# 09_AD.net
KiCad netlist of a schematic drawn in Altium Designer
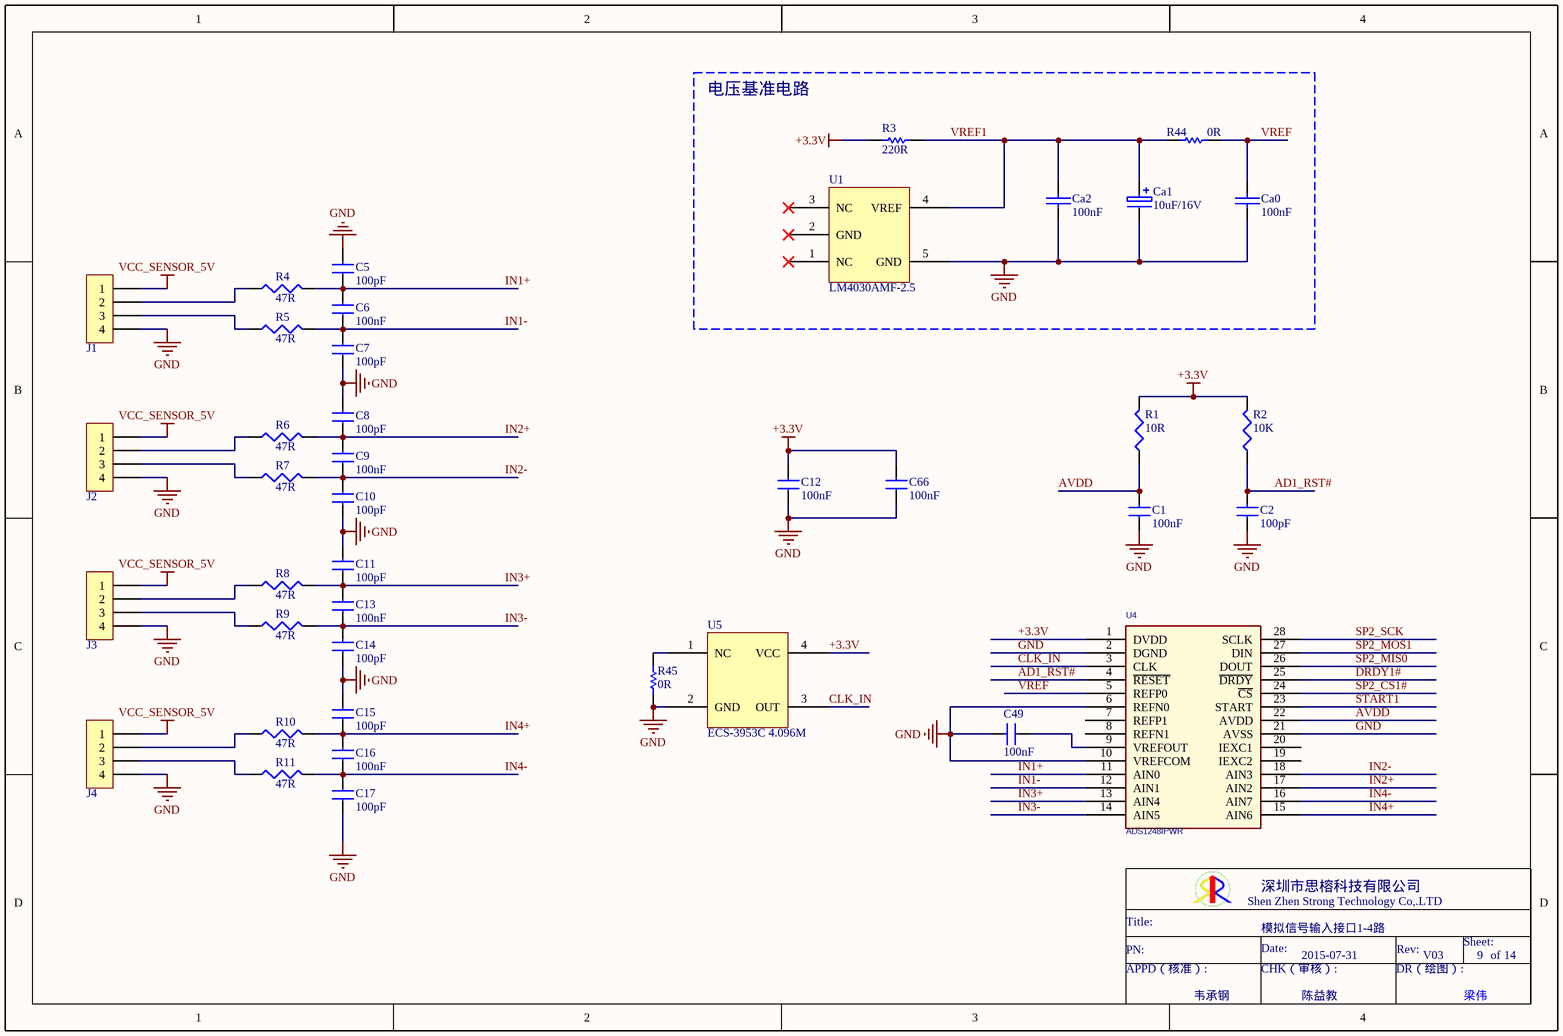
[diagram p0: 09_AD.SchDoc]

(export (version "E")
  (design (tool "Eeschema 10.0.6"))
  (components
    (comp (ref "C1")
      (value "100nF")
      (footprint "0603C")
      (description "Capacitor")
      (libsource (lib "*") (part "电容"))
    )
    (comp (ref "C2")
      (value "100pF")
      (footprint "0603C")
      (description "Capacitor")
      (libsource (lib "*") (part "电容"))
    )
    (comp (ref "C5")
      (value "100pF")
      (footprint "0603C")
      (description "Capacitor")
      (libsource (lib "*") (part "电容"))
    )
    (comp (ref "C6")
      (value "100nF")
      (footprint "0603C")
      (description "Capacitor")
      (libsource (lib "*") (part "电容"))
    )
    (comp (ref "C7")
      (value "100pF")
      (footprint "0603C")
      (description "Capacitor")
      (libsource (lib "*") (part "电容"))
    )
    (comp (ref "C8")
      (value "100pF")
      (footprint "0603C")
      (description "Capacitor")
      (libsource (lib "*") (part "电容"))
    )
    (comp (ref "C9")
      (value "100nF")
      (footprint "0603C")
      (description "Capacitor")
      (libsource (lib "*") (part "电容"))
    )
    (comp (ref "C10")
      (value "100pF")
      (footprint "0603C")
      (description "Capacitor")
      (libsource (lib "*") (part "电容"))
    )
    (comp (ref "C11")
      (value "100pF")
      (footprint "0603C")
      (description "Capacitor")
      (libsource (lib "*") (part "电容"))
    )
    (comp (ref "C12")
      (value "100nF")
      (footprint "0603C")
      (description "Capacitor")
      (libsource (lib "*") (part "电容"))
    )
    (comp (ref "C13")
      (value "100nF")
      (footprint "0603C")
      (description "Capacitor")
      (libsource (lib "*") (part "电容"))
    )
    (comp (ref "C14")
      (value "100pF")
      (footprint "0603C")
      (description "Capacitor")
      (libsource (lib "*") (part "电容"))
    )
    (comp (ref "C15")
      (value "100pF")
      (footprint "0603C")
      (description "Capacitor")
      (libsource (lib "*") (part "电容"))
    )
    (comp (ref "C16")
      (value "100nF")
      (footprint "0603C")
      (description "Capacitor")
      (libsource (lib "*") (part "电容"))
    )
    (comp (ref "C17")
      (value "100pF")
      (footprint "0603C")
      (description "Capacitor")
      (libsource (lib "*") (part "电容"))
    )
    (comp (ref "C49")
      (value "100nF")
      (footprint "0603C")
      (description "Capacitor")
      (libsource (lib "*") (part "电容"))
    )
    (comp (ref "C66")
      (value "100nF")
      (footprint "0603C")
      (description "Capacitor")
      (libsource (lib "*") (part "电容"))
    )
    (comp (ref "Ca0") (value "100nF") (footprint "0603C") (libsource (lib "WeiCHGSCH") (part "CAP")))
    (comp (ref "Ca1") (value "10uF/16V") (footprint "A") (libsource (lib "WeiCHGSCH") (part "CAP2")))
    (comp (ref "Ca2") (value "100nF") (footprint "0603C") (libsource (lib "WeiCHGSCH") (part "CAP")))
    (comp (ref "J1") (value "XH-4A") (footprint "CN4-2.54") (libsource (lib "Mylibrary") (part "CON4")))
    (comp (ref "J2") (value "XH-4A") (footprint "CN4-2.54") (libsource (lib "Mylibrary") (part "CON4")))
    (comp (ref "J3") (value "XH-4A") (footprint "CN4-2.54") (libsource (lib "Mylibrary") (part "CON4")))
    (comp (ref "J4") (value "XH-4A") (footprint "CN4-2.54") (libsource (lib "Mylibrary") (part "CON4")))
    (comp (ref "R1") (value "10R") (footprint "0603R") (libsource (lib "*") (part "RES1")))
    (comp (ref "R2") (value "10K") (footprint "0603R") (libsource (lib "*") (part "RES1")))
    (comp (ref "R3") (value "220R") (footprint "0603R") (libsource (lib "Mylibrary") (part "RES")))
    (comp (ref "R4") (value "47R") (footprint "0603R") (libsource (lib "*") (part "RES1")))
    (comp (ref "R5") (value "47R") (footprint "0603R") (libsource (lib "*") (part "RES1")))
    (comp (ref "R6") (value "47R") (footprint "0603R") (libsource (lib "*") (part "RES1")))
    (comp (ref "R7") (value "47R") (footprint "0603R") (libsource (lib "*") (part "RES1")))
    (comp (ref "R8") (value "47R") (footprint "0603R") (libsource (lib "*") (part "RES1")))
    (comp (ref "R9") (value "47R") (footprint "0603R") (libsource (lib "*") (part "RES1")))
    (comp (ref "R10") (value "47R") (footprint "0603R") (libsource (lib "*") (part "RES1")))
    (comp (ref "R11") (value "47R") (footprint "0603R") (libsource (lib "*") (part "RES1")))
    (comp (ref "R44") (value "0R") (footprint "0603R") (libsource (lib "Mylibrary") (part "RES")))
    (comp (ref "R45") (value "0R") (footprint "0603R") (libsource (lib "Mylibrary") (part "RES")))
    (comp (ref "U1")
      (value "LM4030AMF-2.5")
      (footprint "SOT23-5")
      (description "Voltage adj")
      (fields (field (name "PUBLISHER") "Altium Limited"))
      (libsource (lib "Mylibrary") (part "LM4030"))
    )
    (comp (ref "U4")
      (value "ADS1248IPWR")
      (footprint "SOIC28")
      (description "IC - 10 BIT FET BUS SWITCH")
      (fields (field (name "MANUFACTURER") "Texas Instruments"))
      (libsource (lib "Mylibrary") (part "ADS1248IPWR"))
    )
    (comp (ref "U5")
      (value "ECS-3953C 4.096M")
      (footprint "ECS-3953C")
      (description "贴片晶振")
      (fields (field (name "PUBLISHER") "Altium Limited"))
      (libsource (lib "Mylibrary") (part "ECS-3953C"))
    )
  )
  (nets
    (net (code "1") (name "+3.3V") (class "Default")
      (node (ref "C12") (pin "1") (pinfunction "1_1") (pintype "passive"))
      (node (ref "C66") (pin "2") (pinfunction "2_2") (pintype "passive"))
      (node (ref "R1") (pin "2") (pinfunction "2_2") (pintype "passive"))
      (node (ref "R2") (pin "2") (pinfunction "2_2") (pintype "passive"))
      (node (ref "R3") (pin "2") (pinfunction "2_2") (pintype "passive"))
      (node (ref "U4") (pin "1") (pinfunction "DVDD_1") (pintype "passive"))
      (node (ref "U5") (pin "4") (pinfunction "VCC_4") (pintype "passive"))
    )
    (net (code "2") (name "/AD1_RST#") (class "Default")
      (node (ref "C2") (pin "1") (pinfunction "1_1") (pintype "passive"))
      (node (ref "R2") (pin "1") (pinfunction "1_1") (pintype "passive"))
      (node (ref "U4") (pin "4") (pinfunction "~{RESET}_4") (pintype "passive"))
    )
    (net (code "3") (name "/AVDD") (class "Default")
      (node (ref "C1") (pin "1") (pinfunction "1_1") (pintype "passive"))
      (node (ref "R1") (pin "1") (pinfunction "1_1") (pintype "passive"))
      (node (ref "U4") (pin "22") (pinfunction "AVDD_22") (pintype "passive"))
    )
    (net (code "4") (name "/CLK_IN") (class "Default")
      (node (ref "U4") (pin "3") (pinfunction "CLK_3") (pintype "passive"))
      (node (ref "U5") (pin "3") (pinfunction "OUT_3") (pintype "passive"))
    )
    (net (code "5") (name "/DRDY1#") (class "Default")
      (node (ref "U4") (pin "25") (pinfunction "~{DRDY}_25") (pintype "passive"))
    )
    (net (code "6") (name "/IN1+") (class "Default")
      (node (ref "C5") (pin "2") (pinfunction "2_2") (pintype "passive"))
      (node (ref "C6") (pin "1") (pinfunction "1_1") (pintype "passive"))
      (node (ref "R4") (pin "2") (pinfunction "2_2") (pintype "passive"))
      (node (ref "U4") (pin "11") (pinfunction "AIN0_11") (pintype "passive"))
    )
    (net (code "7") (name "/IN1-") (class "Default")
      (node (ref "C6") (pin "2") (pinfunction "2_2") (pintype "passive"))
      (node (ref "C7") (pin "1") (pinfunction "1_1") (pintype "passive"))
      (node (ref "R5") (pin "2") (pinfunction "2_2") (pintype "passive"))
      (node (ref "U4") (pin "12") (pinfunction "AIN1_12") (pintype "power_in"))
    )
    (net (code "8") (name "/IN2+") (class "Default")
      (node (ref "C8") (pin "2") (pinfunction "2_2") (pintype "passive"))
      (node (ref "C9") (pin "1") (pinfunction "1_1") (pintype "passive"))
      (node (ref "R6") (pin "2") (pinfunction "2_2") (pintype "passive"))
      (node (ref "U4") (pin "17") (pinfunction "AIN2_17") (pintype "passive"))
    )
    (net (code "9") (name "/IN2-") (class "Default")
      (node (ref "C10") (pin "1") (pinfunction "1_1") (pintype "passive"))
      (node (ref "C9") (pin "2") (pinfunction "2_2") (pintype "passive"))
      (node (ref "R7") (pin "2") (pinfunction "2_2") (pintype "passive"))
      (node (ref "U4") (pin "18") (pinfunction "AIN3_18") (pintype "passive"))
    )
    (net (code "10") (name "/IN3+") (class "Default")
      (node (ref "C11") (pin "2") (pinfunction "2_2") (pintype "passive"))
      (node (ref "C13") (pin "1") (pinfunction "1_1") (pintype "passive"))
      (node (ref "R8") (pin "2") (pinfunction "2_2") (pintype "passive"))
      (node (ref "U4") (pin "13") (pinfunction "AIN4_13") (pintype "passive"))
    )
    (net (code "11") (name "/IN3-") (class "Default")
      (node (ref "C13") (pin "2") (pinfunction "2_2") (pintype "passive"))
      (node (ref "C14") (pin "1") (pinfunction "1_1") (pintype "passive"))
      (node (ref "R9") (pin "2") (pinfunction "2_2") (pintype "passive"))
      (node (ref "U4") (pin "14") (pinfunction "AIN5_14") (pintype "passive"))
    )
    (net (code "12") (name "/IN4+") (class "Default")
      (node (ref "C15") (pin "2") (pinfunction "2_2") (pintype "passive"))
      (node (ref "C16") (pin "1") (pinfunction "1_1") (pintype "passive"))
      (node (ref "R10") (pin "2") (pinfunction "2_2") (pintype "passive"))
      (node (ref "U4") (pin "15") (pinfunction "AIN6_15") (pintype "passive"))
    )
    (net (code "13") (name "/IN4-") (class "Default")
      (node (ref "C16") (pin "2") (pinfunction "2_2") (pintype "passive"))
      (node (ref "C17") (pin "1") (pinfunction "1_1") (pintype "passive"))
      (node (ref "R11") (pin "2") (pinfunction "2_2") (pintype "passive"))
      (node (ref "U4") (pin "16") (pinfunction "AIN7_16") (pintype "passive"))
    )
    (net (code "14") (name "/SP2_CS1#") (class "Default")
      (node (ref "U4") (pin "24") (pinfunction "~{CS}_24") (pintype "power_in"))
    )
    (net (code "15") (name "/SP2_MIS0") (class "Default")
      (node (ref "U4") (pin "26") (pinfunction "DOUT_26") (pintype "passive"))
    )
    (net (code "16") (name "/SP2_MOS1") (class "Default")
      (node (ref "U4") (pin "27") (pinfunction "DIN_27") (pintype "passive"))
    )
    (net (code "17") (name "/SP2_SCK") (class "Default")
      (node (ref "U4") (pin "28") (pinfunction "SCLK_28") (pintype "passive"))
    )
    (net (code "18") (name "/START1") (class "Default")
      (node (ref "U4") (pin "23") (pinfunction "START_23") (pintype "passive"))
    )
    (net (code "19") (name "/VREF") (class "Default")
      (node (ref "Ca0") (pin "1") (pinfunction "1_1") (pintype "passive"))
      (node (ref "R44") (pin "2") (pinfunction "2_2") (pintype "passive"))
      (node (ref "U4") (pin "5") (pinfunction "REFP0_5") (pintype "passive"))
    )
    (net (code "20") (name "/VREF1") (class "Default")
      (node (ref "Ca1") (pin "1") (pinfunction "1_1") (pintype "passive"))
      (node (ref "Ca2") (pin "1") (pinfunction "1_1") (pintype "passive"))
      (node (ref "R3") (pin "1") (pinfunction "1_1") (pintype "passive"))
      (node (ref "R44") (pin "1") (pinfunction "1_1") (pintype "passive"))
      (node (ref "U1") (pin "4") (pinfunction "VREF_4") (pintype "passive"))
    )
    (net (code "21") (name "GND") (class "Default")
      (node (ref "C1") (pin "2") (pinfunction "2_2") (pintype "passive"))
      (node (ref "C10") (pin "2") (pinfunction "2_2") (pintype "passive"))
      (node (ref "C11") (pin "1") (pinfunction "1_1") (pintype "passive"))
      (node (ref "C12") (pin "2") (pinfunction "2_2") (pintype "passive"))
      (node (ref "C14") (pin "2") (pinfunction "2_2") (pintype "passive"))
      (node (ref "C15") (pin "1") (pinfunction "1_1") (pintype "passive"))
      (node (ref "C17") (pin "2") (pinfunction "2_2") (pintype "passive"))
      (node (ref "C2") (pin "2") (pinfunction "2_2") (pintype "passive"))
      (node (ref "C49") (pin "2") (pinfunction "2_2") (pintype "passive"))
      (node (ref "C5") (pin "1") (pinfunction "1_1") (pintype "passive"))
      (node (ref "C66") (pin "1") (pinfunction "1_1") (pintype "passive"))
      (node (ref "C7") (pin "2") (pinfunction "2_2") (pintype "passive"))
      (node (ref "C8") (pin "1") (pinfunction "1_1") (pintype "passive"))
      (node (ref "Ca0") (pin "2") (pinfunction "2_2") (pintype "passive"))
      (node (ref "Ca1") (pin "2") (pinfunction "2_2") (pintype "passive"))
      (node (ref "Ca2") (pin "2") (pinfunction "2_2") (pintype "passive"))
      (node (ref "J1") (pin "4") (pinfunction "4_4") (pintype "passive"))
      (node (ref "J2") (pin "4") (pinfunction "4_4") (pintype "passive"))
      (node (ref "J3") (pin "4") (pinfunction "4_4") (pintype "passive"))
      (node (ref "J4") (pin "4") (pinfunction "4_4") (pintype "passive"))
      (node (ref "R45") (pin "1") (pinfunction "1_1") (pintype "passive"))
      (node (ref "U1") (pin "5") (pinfunction "GND_5") (pintype "passive"))
      (node (ref "U4") (pin "10") (pinfunction "VREFCOM_10") (pintype "passive"))
      (node (ref "U4") (pin "2") (pinfunction "DGND_2") (pintype "passive"))
      (node (ref "U4") (pin "21") (pinfunction "AVSS_21") (pintype "passive"))
      (node (ref "U4") (pin "6") (pinfunction "REFN0_6") (pintype "passive"))
      (node (ref "U5") (pin "2") (pinfunction "GND_2") (pintype "passive"))
    )
    (net (code "22") (name "Net-(J1-Pad2)") (class "Default")
      (node (ref "J1") (pin "2") (pinfunction "2_2") (pintype "passive"))
      (node (ref "R4") (pin "1") (pinfunction "1_1") (pintype "passive"))
    )
    (net (code "23") (name "Net-(J1-Pad3)") (class "Default")
      (node (ref "J1") (pin "3") (pinfunction "3_3") (pintype "passive"))
      (node (ref "R5") (pin "1") (pinfunction "1_1") (pintype "passive"))
    )
    (net (code "24") (name "Net-(J2-Pad2)") (class "Default")
      (node (ref "J2") (pin "2") (pinfunction "2_2") (pintype "passive"))
      (node (ref "R6") (pin "1") (pinfunction "1_1") (pintype "passive"))
    )
    (net (code "25") (name "Net-(J2-Pad3)") (class "Default")
      (node (ref "J2") (pin "3") (pinfunction "3_3") (pintype "passive"))
      (node (ref "R7") (pin "1") (pinfunction "1_1") (pintype "passive"))
    )
    (net (code "26") (name "Net-(J3-Pad2)") (class "Default")
      (node (ref "J3") (pin "2") (pinfunction "2_2") (pintype "passive"))
      (node (ref "R8") (pin "1") (pinfunction "1_1") (pintype "passive"))
    )
    (net (code "27") (name "Net-(J3-Pad3)") (class "Default")
      (node (ref "J3") (pin "3") (pinfunction "3_3") (pintype "passive"))
      (node (ref "R9") (pin "1") (pinfunction "1_1") (pintype "passive"))
    )
    (net (code "28") (name "Net-(J4-Pad2)") (class "Default")
      (node (ref "J4") (pin "2") (pinfunction "2_2") (pintype "passive"))
      (node (ref "R10") (pin "1") (pinfunction "1_1") (pintype "passive"))
    )
    (net (code "29") (name "Net-(J4-Pad3)") (class "Default")
      (node (ref "J4") (pin "3") (pinfunction "3_3") (pintype "passive"))
      (node (ref "R11") (pin "1") (pinfunction "1_1") (pintype "passive"))
    )
    (net (code "30") (name "Net-(U4-VREFOUT)") (class "Default")
      (node (ref "C49") (pin "1") (pinfunction "1_1") (pintype "passive"))
      (node (ref "U4") (pin "9") (pinfunction "VREFOUT_9") (pintype "passive"))
    )
    (net (code "31") (name "Net-(U5-NC)") (class "Default")
      (node (ref "R45") (pin "2") (pinfunction "2_2") (pintype "passive"))
      (node (ref "U5") (pin "1") (pinfunction "NC_1") (pintype "passive"))
    )
    (net (code "32") (name "VCC_SENSOR_5V") (class "Default")
      (node (ref "J1") (pin "1") (pinfunction "1_1") (pintype "passive"))
      (node (ref "J2") (pin "1") (pinfunction "1_1") (pintype "passive"))
      (node (ref "J3") (pin "1") (pinfunction "1_1") (pintype "passive"))
      (node (ref "J4") (pin "1") (pinfunction "1_1") (pintype "passive"))
    )
    (net (code "33") (name "unconnected-(U1-GND-Pad2)") (class "Default")
      (node (ref "U1") (pin "2") (pinfunction "GND_2") (pintype "passive+no_connect"))
    )
    (net (code "34") (name "unconnected-(U1-NC-Pad1)") (class "Default")
      (node (ref "U1") (pin "1") (pinfunction "NC_1") (pintype "passive+no_connect"))
    )
    (net (code "35") (name "unconnected-(U1-NC-Pad3)") (class "Default")
      (node (ref "U1") (pin "3") (pinfunction "NC_3") (pintype "passive+no_connect"))
    )
    (net (code "36") (name "unconnected-(U4-IEXC1-Pad20)") (class "Default")
      (node (ref "U4") (pin "20") (pinfunction "IEXC1_20") (pintype "passive"))
    )
    (net (code "37") (name "unconnected-(U4-IEXC2-Pad19)") (class "Default")
      (node (ref "U4") (pin "19") (pinfunction "IEXC2_19") (pintype "passive"))
    )
    (net (code "38") (name "unconnected-(U4-REFN1-Pad8)") (class "Default")
      (node (ref "U4") (pin "8") (pinfunction "REFN1_8") (pintype "passive"))
    )
    (net (code "39") (name "unconnected-(U4-REFP1-Pad7)") (class "Default")
      (node (ref "U4") (pin "7") (pinfunction "REFP1_7") (pintype "passive"))
    )
  )
)
